# unicorder-temp-mk-3_0.net
KiCad netlist of a schematic drawn in EAGLE
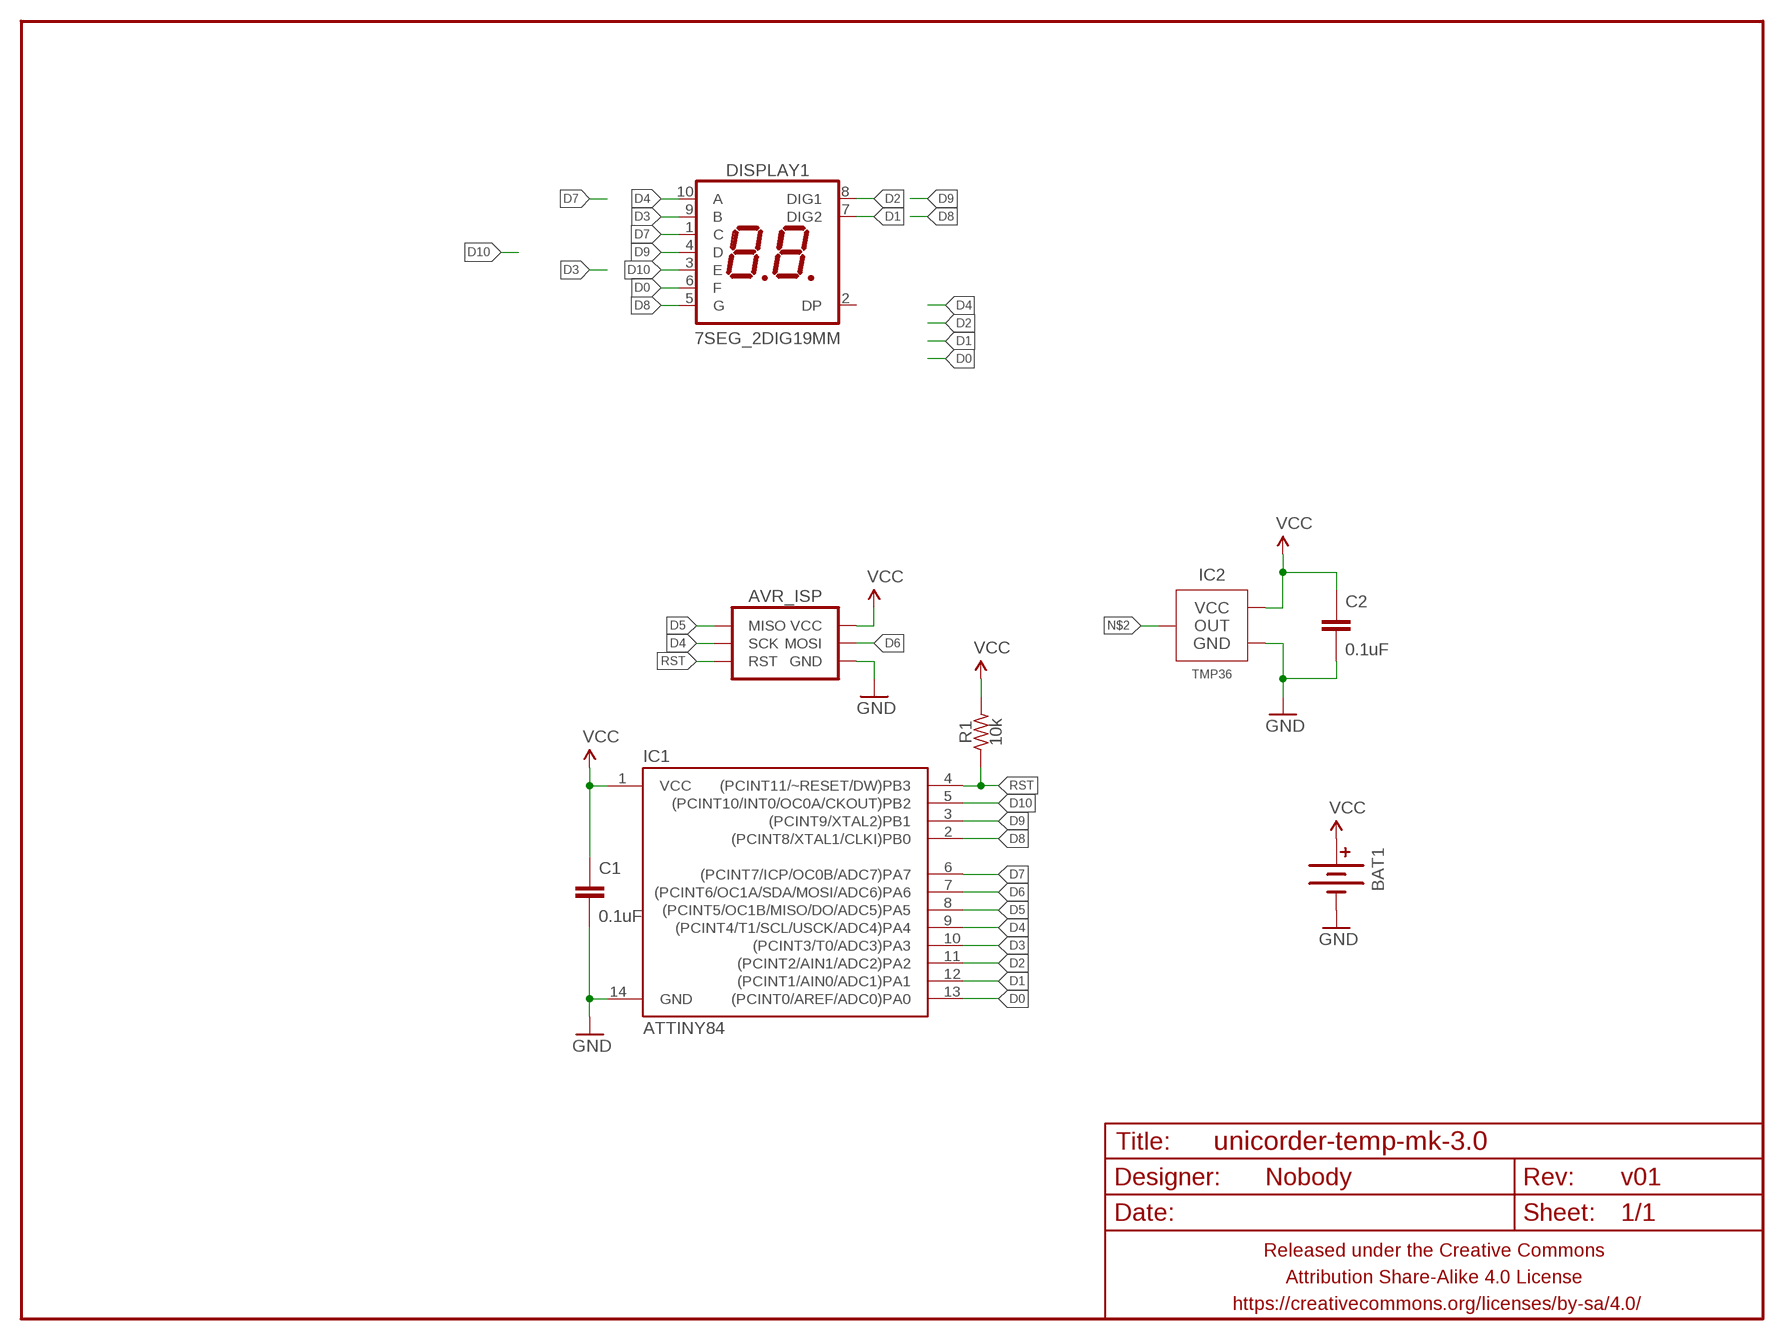
[diagram p0: schematic, sheet 1]

(export (version "E")
  (design (tool "Eeschema 10.0.6"))
  (components
    (comp (ref "AVR_ISP")
      (value "AVR_SPI_PRG_6SMD_TEST_POINTS")
      (footprint "eagle-import:2X3_SMD_TEST_POINTS")
      (libsource (lib "eagle-import") (part "AVR_SPI_PRG_6SMD_TEST_POINTS"))
    )
    (comp (ref "BAT1")
      (value "BATTERY20PTH_TOPLOAD")
      (footprint "eagle-import:BATTCON_20MM_PTH_TOPLOAD")
      (libsource (lib "eagle-import") (part "BATTERY20PTH_TOPLOAD"))
    )
    (comp (ref "C1")
      (value "0.1uF")
      (footprint "eagle-import:C0805")
      (libsource (lib "eagle-import") (part "CAPACITOR-CERAMICC0805"))
    )
    (comp (ref "C2")
      (value "0.1uF")
      (footprint "eagle-import:C025-024X044")
      (libsource (lib "eagle-import") (part "CAPACITOR-CERAMIC025-024X044"))
    )
    (comp (ref "DISPLAY1")
      (value "7SEG_2DIG19MM")
      (footprint "eagle-import:7SEG_2DIG_19MM")
      (libsource (lib "eagle-import") (part "7SEG_2DIG19MM"))
    )
    (comp (ref "FRAME1")
      (value "FRAME-LETTERNO_PACKAGE")
      (footprint "eagle-import:DUMMY")
      (fields (field (name "DESIGNER") "Nobody"))
      (libsource (lib "eagle-import") (part "FRAME-LETTERNO_PACKAGE"))
    )
    (comp (ref "IC1")
      (value "ATTINY84")
      (footprint "eagle-import:SO14")
      (libsource (lib "eagle-import") (part "ATTINY84"))
    )
    (comp (ref "IC2")
      (value "TMP36")
      (footprint "eagle-import:TO-92-AMMO")
      (libsource (lib "eagle-import") (part "TMP36TO-92"))
    )
    (comp (ref "R1")
      (value "10k")
      (footprint "eagle-import:R0805")
      (libsource (lib "eagle-import") (part "RESISTORR0805"))
    )
  )
  (nets
    (net (code "1") (name "D0") (class "Default")
      (node (ref "DISPLAY1") (pin "6") (pinfunction "F_6") (pintype "passive"))
      (node (ref "IC1") (pin "13") (pinfunction "(PCINT0/AREF/ADC0)PA0_13") (pintype "bidirectional"))
    )
    (net (code "2") (name "D1") (class "Default")
      (node (ref "DISPLAY1") (pin "7") (pinfunction "DIG2_7") (pintype "passive"))
      (node (ref "IC1") (pin "12") (pinfunction "(PCINT1/AIN0/ADC1)PA1_12") (pintype "bidirectional"))
    )
    (net (code "3") (name "D2") (class "Default")
      (node (ref "DISPLAY1") (pin "8") (pinfunction "DIG1_8") (pintype "passive"))
      (node (ref "IC1") (pin "11") (pinfunction "(PCINT2/AIN1/ADC2)PA2_11") (pintype "bidirectional"))
    )
    (net (code "4") (name "D3") (class "Default")
      (node (ref "DISPLAY1") (pin "9") (pinfunction "B_9") (pintype "passive"))
      (node (ref "IC1") (pin "10") (pinfunction "(PCINT3/T0/ADC3)PA3_10") (pintype "bidirectional"))
    )
    (net (code "5") (name "D4") (class "Default")
      (node (ref "AVR_ISP") (pin "3") (pinfunction "SCK_3") (pintype "passive"))
      (node (ref "DISPLAY1") (pin "10") (pinfunction "A_10") (pintype "passive"))
      (node (ref "IC1") (pin "9") (pinfunction "(PCINT4/T1/SCL/USCK/ADC4)PA4_9") (pintype "bidirectional"))
    )
    (net (code "6") (name "D5") (class "Default")
      (node (ref "AVR_ISP") (pin "1") (pinfunction "MISO_1") (pintype "passive"))
      (node (ref "IC1") (pin "8") (pinfunction "(PCINT5/OC1B/MISO/DO/ADC5)PA5_8") (pintype "bidirectional"))
    )
    (net (code "7") (name "D6") (class "Default")
      (node (ref "AVR_ISP") (pin "4") (pinfunction "MOSI_4") (pintype "passive"))
      (node (ref "IC1") (pin "7") (pinfunction "(PCINT6/OC1A/SDA/MOSI/ADC6)PA6_7") (pintype "bidirectional"))
    )
    (net (code "8") (name "D7") (class "Default")
      (node (ref "DISPLAY1") (pin "1") (pinfunction "C_1") (pintype "passive"))
      (node (ref "IC1") (pin "6") (pinfunction "(PCINT7/ICP/OC0B/ADC7)PA7_6") (pintype "bidirectional"))
    )
    (net (code "9") (name "D8") (class "Default")
      (node (ref "DISPLAY1") (pin "5") (pinfunction "G_5") (pintype "passive"))
      (node (ref "IC1") (pin "2") (pinfunction "(PCINT8/XTAL1/CLKI)PB0_2") (pintype "bidirectional"))
    )
    (net (code "10") (name "D9") (class "Default")
      (node (ref "DISPLAY1") (pin "4") (pinfunction "D_4") (pintype "passive"))
      (node (ref "IC1") (pin "3") (pinfunction "(PCINT9/XTAL2)PB1_3") (pintype "bidirectional"))
    )
    (net (code "11") (name "D10") (class "Default")
      (node (ref "DISPLAY1") (pin "3") (pinfunction "E_3") (pintype "passive"))
      (node (ref "IC1") (pin "5") (pinfunction "(PCINT10/INT0/OC0A/CKOUT)PB2_5") (pintype "bidirectional"))
    )
    (net (code "12") (name "GND") (class "Default")
      (node (ref "AVR_ISP") (pin "6") (pinfunction "GND_6") (pintype "passive"))
      (node (ref "BAT1") (pin "-") (pinfunction "-_-") (pintype "power_in"))
      (node (ref "C1") (pin "2") (pinfunction "2_2") (pintype "passive"))
      (node (ref "C2") (pin "2") (pinfunction "2_2") (pintype "passive"))
      (node (ref "IC1") (pin "14") (pinfunction "GND_14") (pintype "bidirectional"))
      (node (ref "IC2") (pin "3") (pinfunction "GND_3") (pintype "bidirectional"))
    )
    (net (code "13") (name "N$2") (class "Default")
      (node (ref "IC2") (pin "2") (pinfunction "OUT_2") (pintype "bidirectional"))
    )
    (net (code "14") (name "RST") (class "Default")
      (node (ref "AVR_ISP") (pin "5") (pinfunction "RST_5") (pintype "passive"))
      (node (ref "IC1") (pin "4") (pinfunction "(PCINT11/~{RESET/DW})PB3_4") (pintype "bidirectional"))
      (node (ref "R1") (pin "1") (pinfunction "1_1") (pintype "passive"))
    )
    (net (code "15") (name "VCC") (class "Default")
      (node (ref "AVR_ISP") (pin "2") (pinfunction "VCC_2") (pintype "passive"))
      (node (ref "BAT1") (pin "+") (pinfunction "+_+") (pintype "power_in"))
      (node (ref "C1") (pin "1") (pinfunction "1_1") (pintype "passive"))
      (node (ref "C2") (pin "1") (pinfunction "1_1") (pintype "passive"))
      (node (ref "IC1") (pin "1") (pinfunction "VCC_1") (pintype "bidirectional"))
      (node (ref "IC2") (pin "1") (pinfunction "VCC_1") (pintype "bidirectional"))
      (node (ref "R1") (pin "2") (pinfunction "2_2") (pintype "passive"))
    )
    (net (code "16") (name "unconnected-(DISPLAY1-DP-Pad2)") (class "Default")
      (node (ref "DISPLAY1") (pin "2") (pinfunction "DP_2") (pintype "passive"))
    )
  )
)
